# Sw_reset_spno.net
KiCad netlist of a schematic drawn in Altium Designer
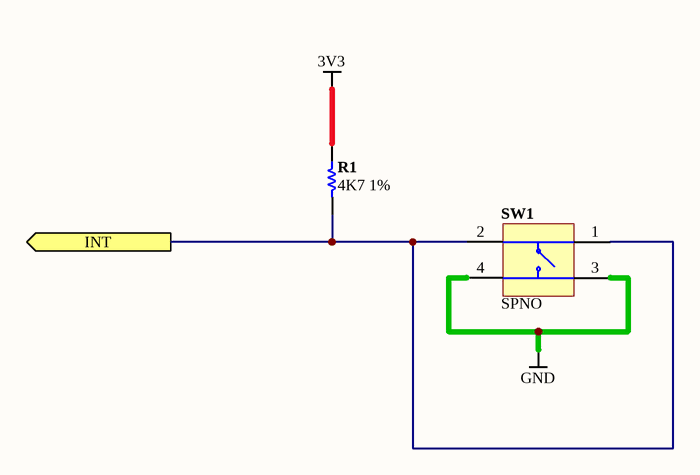
[diagram p0: Sw_reset_spno.schdoc]

(export (version "E")
  (design (tool "Eeschema 10.0.6"))
  (components
    (comp (ref "R1")
      (value "4K7 1%")
      (footprint "RESC1005-STAR")
      (description "Resistor, 4K7 1% 0402 (1005)")
      (fields (field (name "TOLERANCE") "1 %"))
      (libsource (lib "altium-import") (part "root_0_mirrored_RES_"))
    )
    (comp (ref "SW1")
      (value "SPNO")
      (footprint "SW_DTSM-61NT/R")
      (description "Switch, SPNO Push Button SMD")
      (libsource (lib "AltiumDesignLibrary") (part "SWI-PB-SPNO"))
    )
  )
  (nets
    (net (code "1") (name "/INT") (class "Default")
      (node (ref "R1") (pin "2") (pinfunction "2_2") (pintype "passive"))
      (node (ref "SW1") (pin "1") (pinfunction "1_1") (pintype "passive"))
      (node (ref "SW1") (pin "2") (pinfunction "2_2") (pintype "passive"))
    )
    (net (code "2") (name "3V3") (class "Default")
      (node (ref "R1") (pin "1") (pinfunction "1_1") (pintype "passive"))
    )
    (net (code "3") (name "GND") (class "Default")
      (node (ref "SW1") (pin "3") (pinfunction "3_3") (pintype "passive"))
      (node (ref "SW1") (pin "4") (pinfunction "4_4") (pintype "passive"))
    )
  )
)
